# Memory.net
KiCad netlist of a schematic drawn in Altium Designer
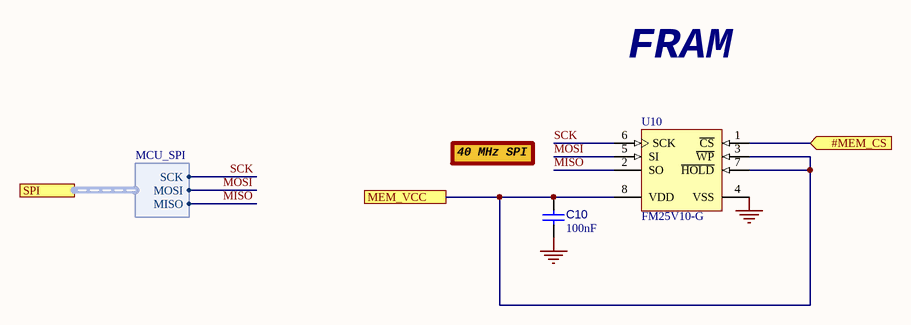
[diagram p0: Memory.SchDoc]

(export (version "E")
  (design (tool "Eeschema 10.0.6"))
  (components
    (comp (ref "C10")
      (value "100nF")
      (footprint "CAPC0402(1005)60_L")
      (description "Chip Capacitor, 100nF +/-20%, 25V, 0402, Thickness 0.6 mm")
      (fields (field (name "TOLERANCE") "10%") (field (name "Comment") "Capacitor 100nF +/-20% 25V 0402"))
      (libsource (lib "Ka Moamoa") (part "CAP-NP-2"))
    )
    (comp (ref "U10")
      (value "FM25V10-G")
      (footprint "SOIC127P600X173-8N")
      (description "1-Mbit Serial F-RAM, 2 to 3.6 V, -40 to 85 degC, 8-Pin SOIC (S08.15), RoHS, Tube")
      (fields (field (name "GENERIC PART NUMBER") "FM25V10"))
      (libsource (lib "Ka Moamoa") (part "CYP-FM25V10-G-8"))
    )
  )
  (nets
    (net (code "2") (name "/#MEM_CS") (class "Default")
      (node (ref "U10") (pin "1") (pinfunction "~{CS}_1") (pintype "input"))
    )
    (net (code "3") (name "/MEM_VCC") (class "Default")
      (node (ref "C10") (pin "1") (pinfunction "1_1") (pintype "passive"))
      (node (ref "U10") (pin "3") (pinfunction "~{WP}_3") (pintype "input"))
      (node (ref "U10") (pin "7") (pinfunction "~{HOLD}_7") (pintype "input"))
      (node (ref "U10") (pin "8") (pinfunction "VDD_8") (pintype "power_in"))
    )
    (net (code "4") (name "/MISO") (class "Default")
      (node (ref "U10") (pin "2") (pinfunction "SO_2") (pintype "tri_state"))
    )
    (net (code "5") (name "/MOSI") (class "Default")
      (node (ref "U10") (pin "5") (pinfunction "SI_5") (pintype "input"))
    )
    (net (code "6") (name "/SCK") (class "Default")
      (node (ref "U10") (pin "6") (pinfunction "SCK_6") (pintype "input"))
    )
    (net (code "8") (name "GND") (class "Default")
      (node (ref "C10") (pin "2") (pinfunction "2_2") (pintype "passive"))
      (node (ref "U10") (pin "4") (pinfunction "VSS_4") (pintype "power_in"))
    )
  )
)
